# mpp_bldc.net
KiCad netlist of a schematic drawn in EAGLE
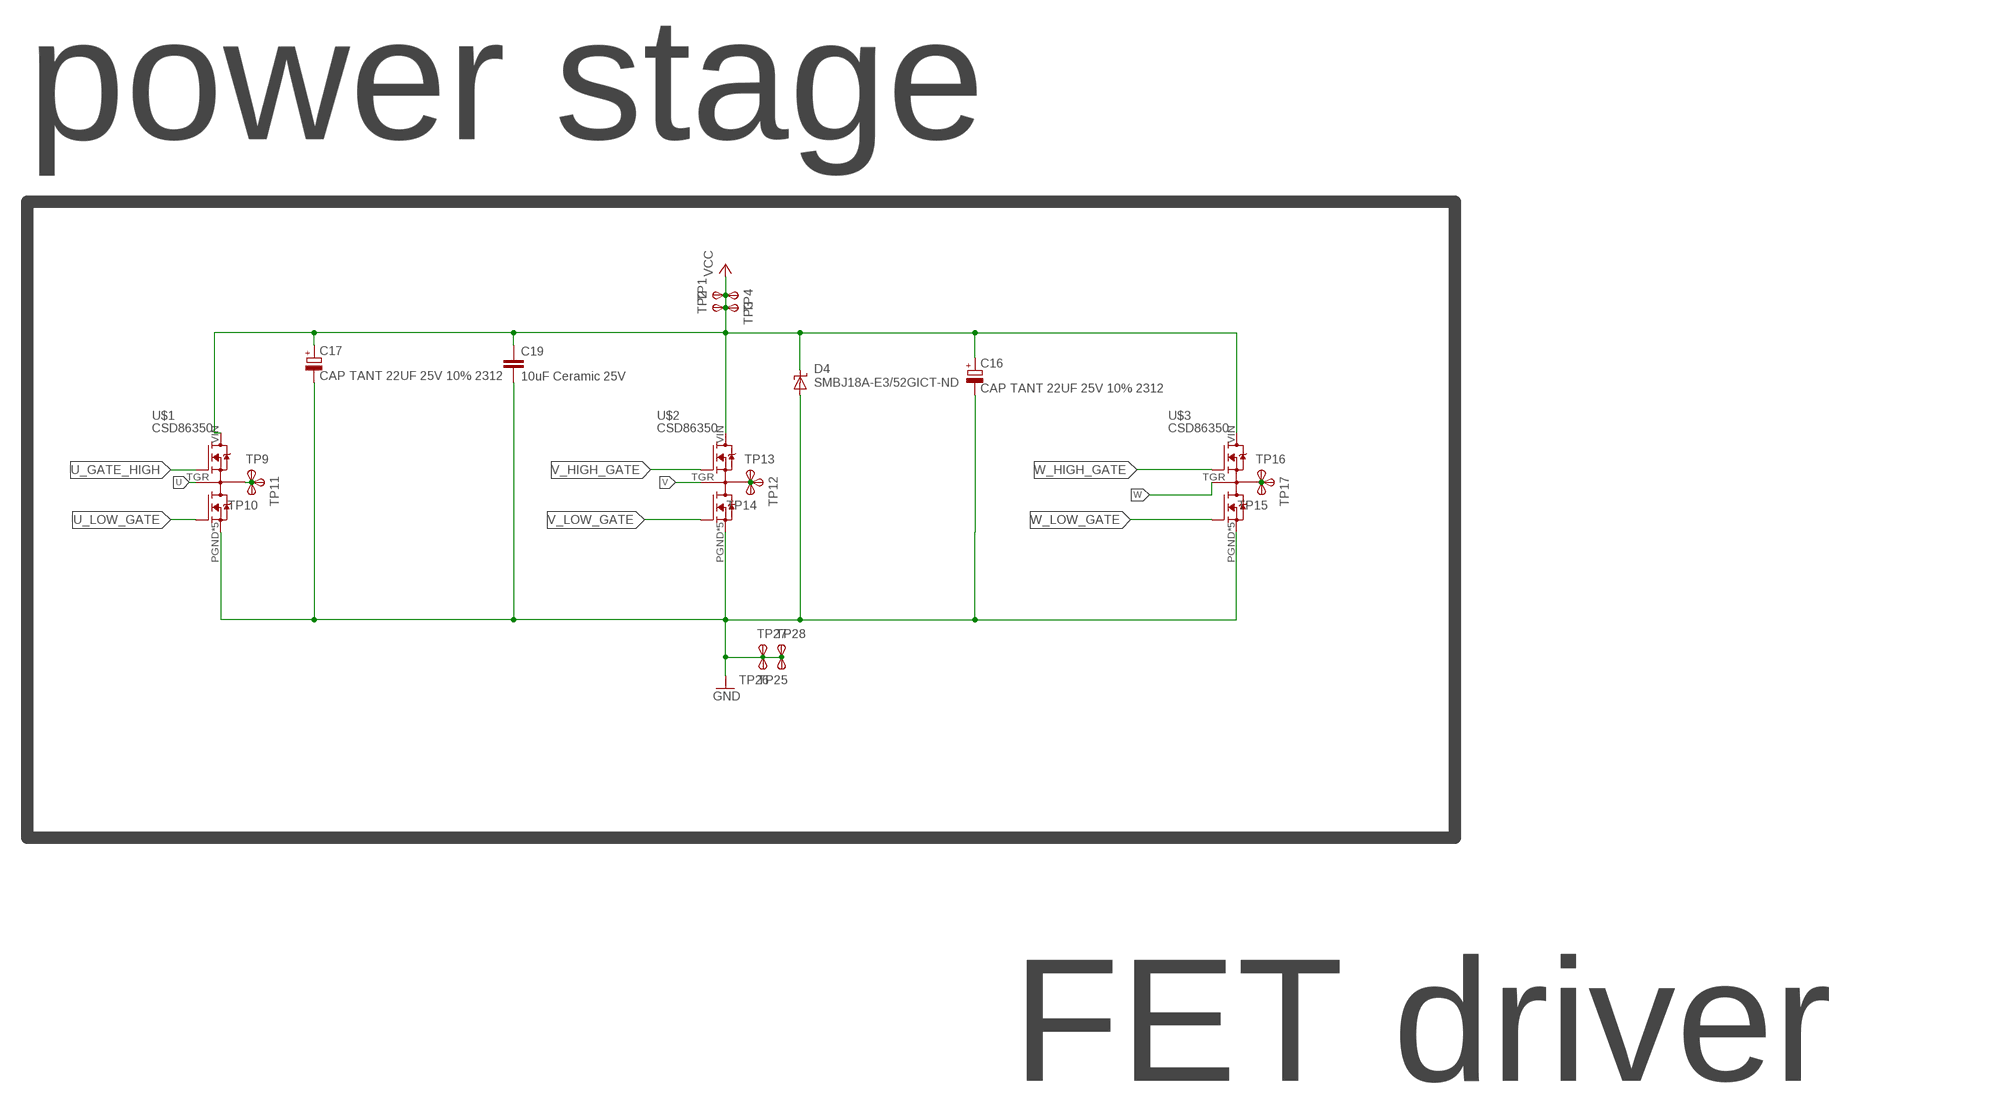
[diagram p0: schematic, sheet 1, part 1 of 2]
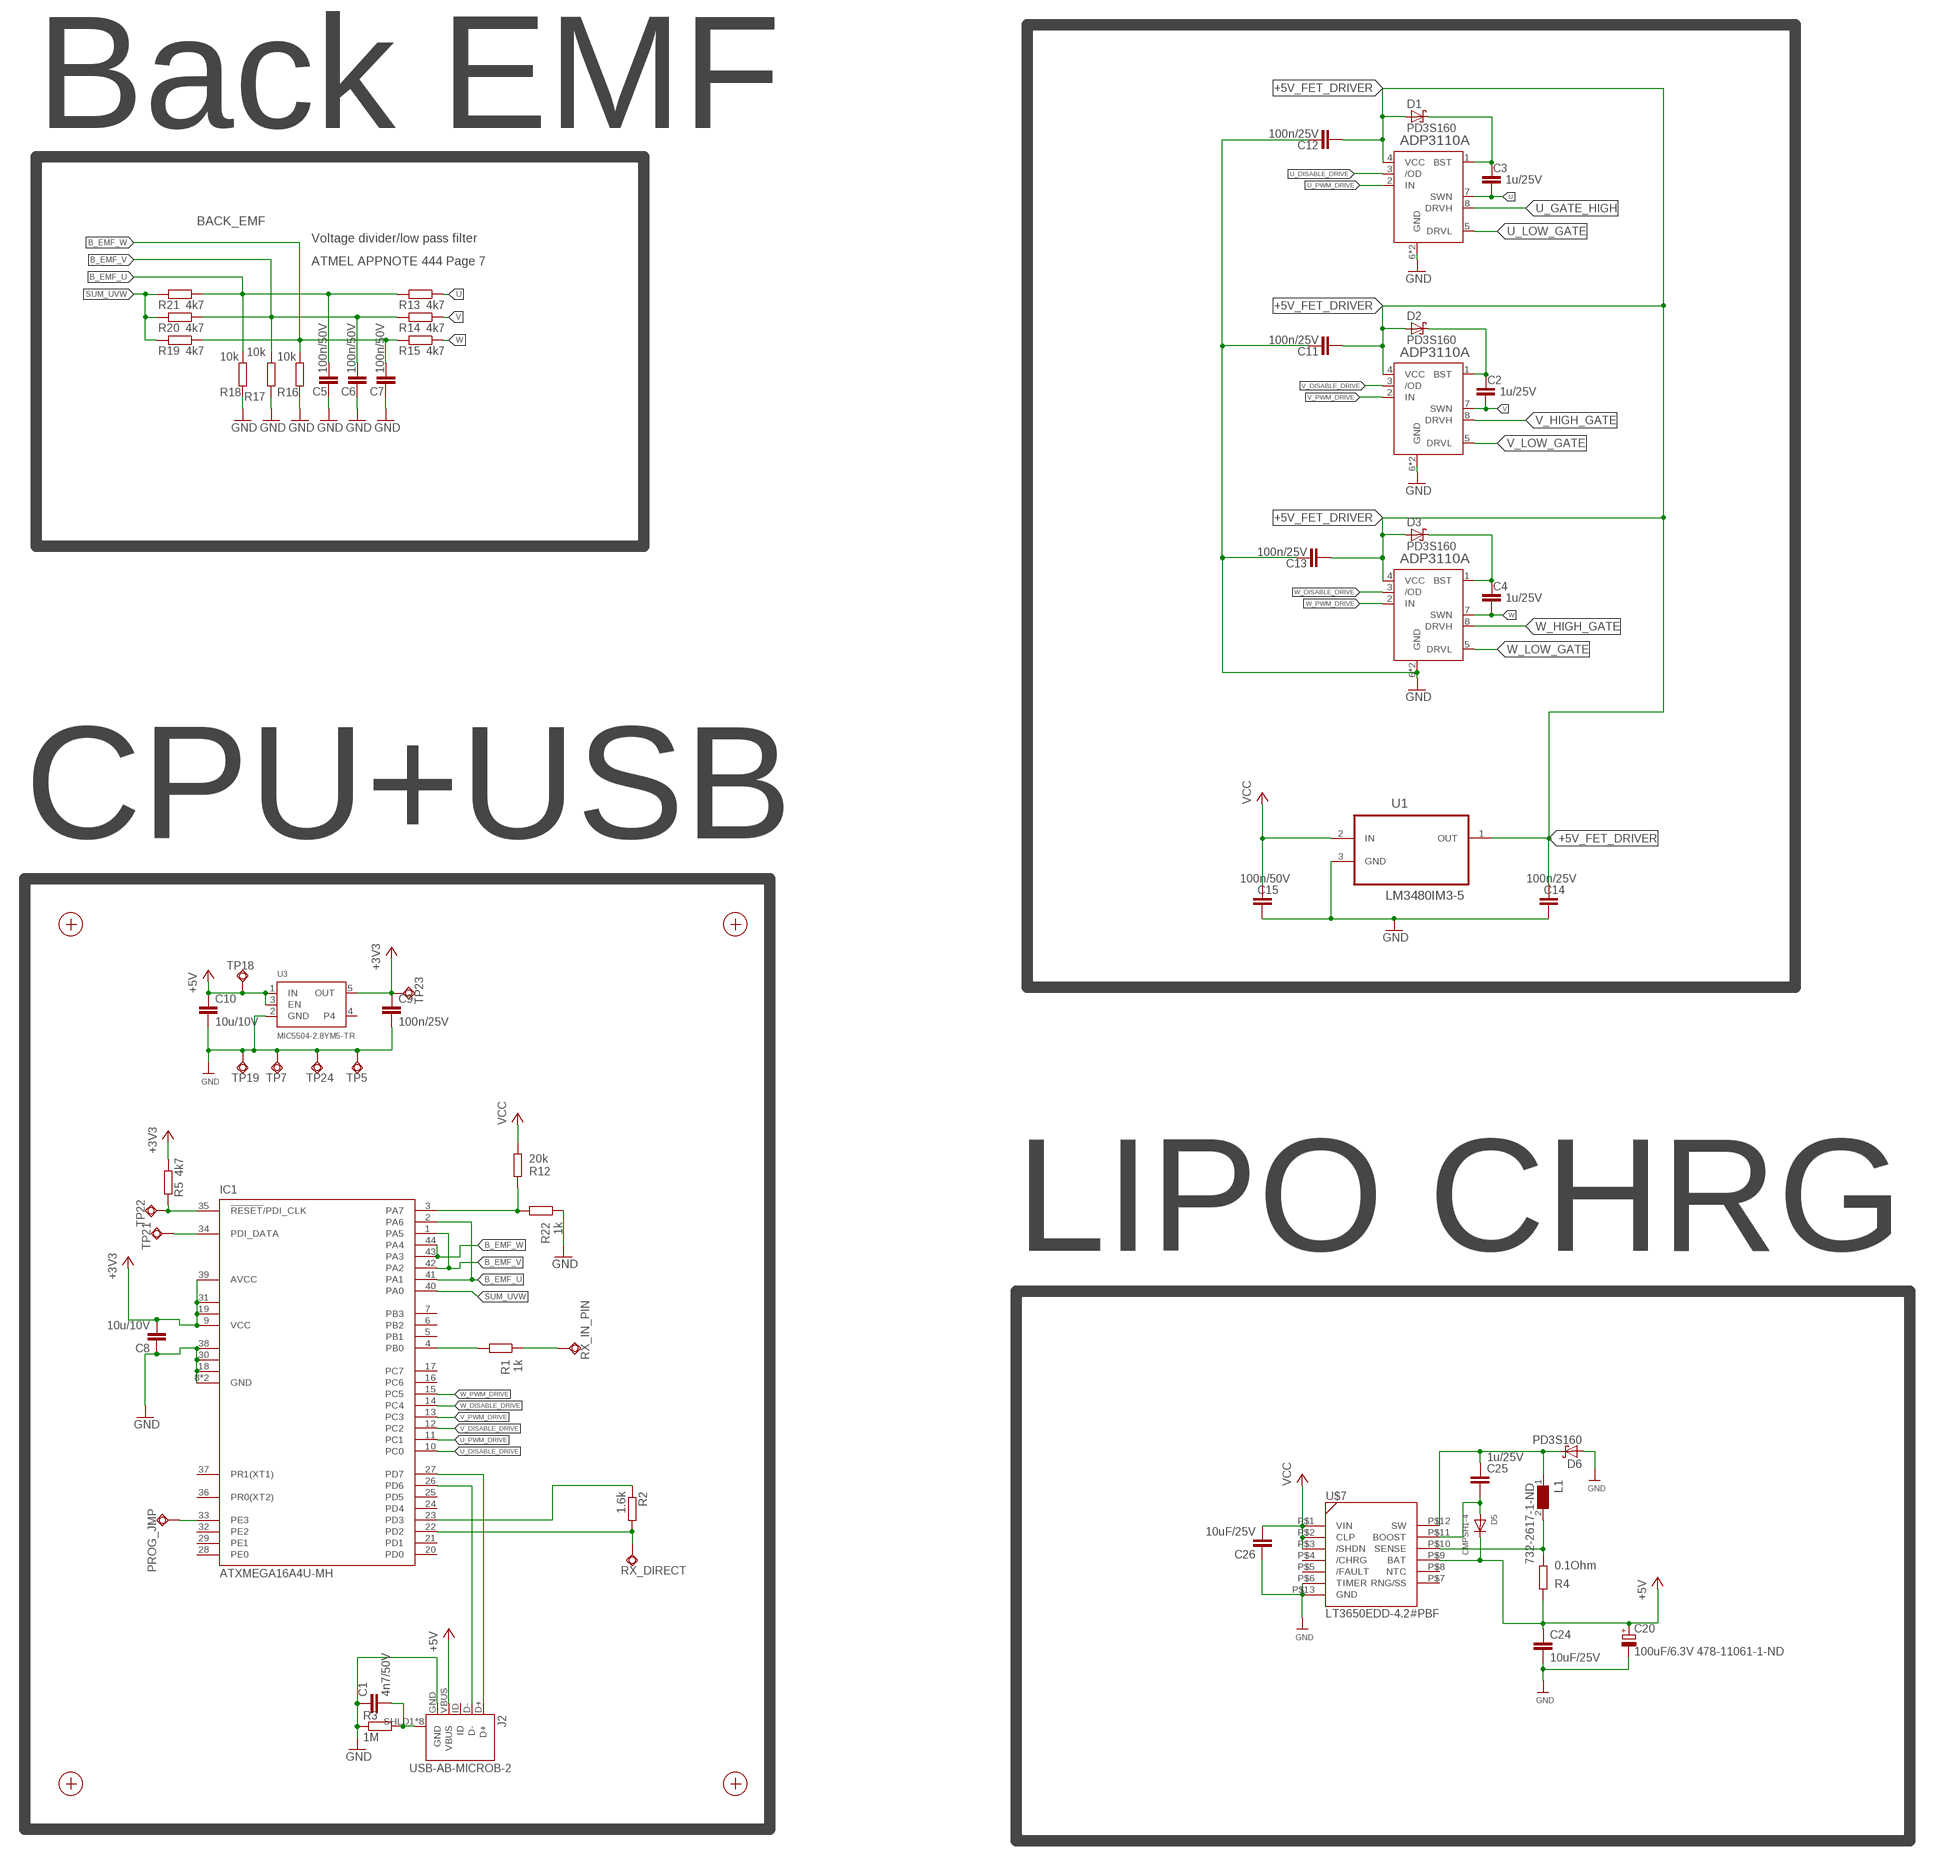
[diagram p1: schematic, sheet 1, part 2 of 2]

(export (version "E")
  (design (tool "Eeschema 10.0.6"))
  (components
    (comp (ref "C1")
      (value "4n7/50V")
      (footprint "eagle-import:C0603")
      (libsource (lib "eagle-import") (part "C-EUC0603"))
    )
    (comp (ref "C2")
      (value "1u/25V")
      (footprint "eagle-import:C0603")
      (libsource (lib "eagle-import") (part "C-EUC0603"))
    )
    (comp (ref "C3")
      (value "1u/25V")
      (footprint "eagle-import:C0603")
      (libsource (lib "eagle-import") (part "C-EUC0603"))
    )
    (comp (ref "C4")
      (value "1u/25V")
      (footprint "eagle-import:C0603")
      (libsource (lib "eagle-import") (part "C-EUC0603"))
    )
    (comp (ref "C5")
      (value "100n/50V")
      (footprint "eagle-import:C0603")
      (libsource (lib "eagle-import") (part "C-EUC0603"))
    )
    (comp (ref "C6")
      (value "100n/50V")
      (footprint "eagle-import:C0603")
      (libsource (lib "eagle-import") (part "C-EUC0603"))
    )
    (comp (ref "C7")
      (value "100n/50V")
      (footprint "eagle-import:C0603")
      (libsource (lib "eagle-import") (part "C-EUC0603"))
    )
    (comp (ref "C8")
      (value "10u/10V")
      (footprint "eagle-import:C0603K")
      (libsource (lib "eagle-import") (part "C-EUC0603K"))
    )
    (comp (ref "C9")
      (value "100n/25V")
      (footprint "eagle-import:C0603")
      (libsource (lib "eagle-import") (part "C-EUC0603"))
    )
    (comp (ref "C10")
      (value "10u/10V")
      (footprint "eagle-import:C0603K")
      (libsource (lib "eagle-import") (part "C-EUC0603K"))
    )
    (comp (ref "C11")
      (value "100n/25V")
      (footprint "eagle-import:C0603")
      (libsource (lib "eagle-import") (part "C-EUC0603"))
    )
    (comp (ref "C12")
      (value "100n/25V")
      (footprint "eagle-import:C0603")
      (libsource (lib "eagle-import") (part "C-EUC0603"))
    )
    (comp (ref "C13")
      (value "100n/25V")
      (footprint "eagle-import:C0603")
      (libsource (lib "eagle-import") (part "C-EUC0603"))
    )
    (comp (ref "C14")
      (value "100n/25V")
      (footprint "eagle-import:C0603")
      (libsource (lib "eagle-import") (part "C-EUC0603"))
    )
    (comp (ref "C15")
      (value "100n/50V")
      (footprint "eagle-import:C0603")
      (libsource (lib "eagle-import") (part "C-EUC0603"))
    )
    (comp (ref "C16")
      (value "CAP TANT 22UF 25V 10% 2312")
      (footprint "eagle-import:C_6032-28R")
      (libsource (lib "eagle-import") (part "CPOL-EUC/6032-28R"))
    )
    (comp (ref "C17")
      (value "CAP TANT 22UF 25V 10% 2312")
      (footprint "eagle-import:C_6032-28R")
      (libsource (lib "eagle-import") (part "CPOL-EUC/6032-28R"))
    )
    (comp (ref "C19")
      (value "10uF Ceramic 25V")
      (footprint "eagle-import:C1206")
      (libsource (lib "eagle-import") (part "rcl_334_C-EUC1206"))
    )
    (comp (ref "C20")
      (value "100uF/6.3V 478-11061-1-ND")
      (footprint "eagle-import:CT7343")
      (libsource (lib "eagle-import") (part "CPOL-EUCT7343"))
    )
    (comp (ref "C24")
      (value "10uF/25V")
      (footprint "eagle-import:C0805")
      (libsource (lib "eagle-import") (part "C-EUC0805"))
    )
    (comp (ref "C25")
      (value "1u/25V")
      (footprint "eagle-import:C0603")
      (libsource (lib "eagle-import") (part "C-EUC0603"))
    )
    (comp (ref "C26")
      (value "10uF/25V")
      (footprint "eagle-import:C0805")
      (libsource (lib "eagle-import") (part "C-EUC0805"))
    )
    (comp (ref "D1")
      (value "PD3S160")
      (footprint "eagle-import:POWERDI323")
      (libsource (lib "eagle-import") (part "mpp_bldc_ng_2_PD3S160"))
    )
    (comp (ref "D2")
      (value "PD3S160")
      (footprint "eagle-import:POWERDI323")
      (libsource (lib "eagle-import") (part "mpp_bldc_ng_2_PD3S160"))
    )
    (comp (ref "D3")
      (value "PD3S160")
      (footprint "eagle-import:POWERDI323")
      (libsource (lib "eagle-import") (part "mpp_bldc_ng_2_PD3S160"))
    )
    (comp (ref "D4")
      (value "SMBJ18A-E3/52GICT-ND")
      (footprint "eagle-import:SMBJ")
      (libsource (lib "eagle-import") (part "SUPPRESSOR-SMBJ"))
    )
    (comp (ref "D5")
      (value "CMPSH1-4")
      (footprint "eagle-import:SOT23-R")
      (libsource (lib "eagle-import") (part "DIODESOT23_REFLOW"))
    )
    (comp (ref "D6")
      (value "PD3S160")
      (footprint "eagle-import:POWERDI323")
      (libsource (lib "eagle-import") (part "PD3S160"))
    )
    (comp (ref "IC1")
      (value "ATXMEGA16A4U-MH")
      (footprint "eagle-import:MLF44-TH")
      (libsource (lib "eagle-import") (part "XMEGA16A4M1"))
    )
    (comp (ref "J2")
      (value "USB-AB-MICROB-2")
      (footprint "eagle-import:USB-MICROB-10118194")
      (libsource (lib "eagle-import") (part "USB-AB-MICROB-2"))
    )
    (comp (ref "L1")
      (value "732-2617-1-ND")
      (footprint "eagle-import:WE-TPC_2828")
      (fields (field (name "MPN") "744025001"))
      (libsource (lib "eagle-import") (part "WE-TPC_2828-744025001"))
    )
    (comp (ref "PROG_JMP")
      (value "TPSQTP19SQ")
      (footprint "eagle-import:TP19SQ")
      (libsource (lib "eagle-import") (part "TPSQTP19SQ"))
    )
    (comp (ref "R1")
      (value "1k")
      (footprint "eagle-import:R0603")
      (libsource (lib "eagle-import") (part "R-EU_R0603"))
    )
    (comp (ref "R2")
      (value "1.6k")
      (footprint "eagle-import:R0603")
      (libsource (lib "eagle-import") (part "resistor_R-EU_R0603"))
    )
    (comp (ref "R3")
      (value "1M")
      (footprint "eagle-import:R0603")
      (libsource (lib "eagle-import") (part "resistor_R-EU_R0603"))
    )
    (comp (ref "R4")
      (value "0.1Ohm")
      (footprint "eagle-import:R0402")
      (libsource (lib "eagle-import") (part "R-EU_R0402"))
    )
    (comp (ref "R5")
      (value "4k7")
      (footprint "eagle-import:R0603")
      (libsource (lib "eagle-import") (part "R-EU_R0603"))
    )
    (comp (ref "R12")
      (value "20k")
      (footprint "eagle-import:R0603")
      (libsource (lib "eagle-import") (part "R-EU_R0603"))
    )
    (comp (ref "R13")
      (value "4k7")
      (footprint "eagle-import:R0603")
      (libsource (lib "eagle-import") (part "R-EU_R0603"))
    )
    (comp (ref "R14")
      (value "4k7")
      (footprint "eagle-import:R0603")
      (libsource (lib "eagle-import") (part "R-EU_R0603"))
    )
    (comp (ref "R15")
      (value "4k7")
      (footprint "eagle-import:R0603")
      (libsource (lib "eagle-import") (part "R-EU_R0603"))
    )
    (comp (ref "R16")
      (value "10k")
      (footprint "eagle-import:R0603")
      (libsource (lib "eagle-import") (part "R-EU_R0603"))
    )
    (comp (ref "R17")
      (value "10k")
      (footprint "eagle-import:R0603")
      (libsource (lib "eagle-import") (part "R-EU_R0603"))
    )
    (comp (ref "R18")
      (value "10k")
      (footprint "eagle-import:R0603")
      (libsource (lib "eagle-import") (part "R-EU_R0603"))
    )
    (comp (ref "R19")
      (value "4k7")
      (footprint "eagle-import:R0603")
      (libsource (lib "eagle-import") (part "R-EU_R0603"))
    )
    (comp (ref "R20")
      (value "4k7")
      (footprint "eagle-import:R0603")
      (libsource (lib "eagle-import") (part "R-EU_R0603"))
    )
    (comp (ref "R21")
      (value "4k7")
      (footprint "eagle-import:R0603")
      (libsource (lib "eagle-import") (part "R-EU_R0603"))
    )
    (comp (ref "R22")
      (value "1k")
      (footprint "eagle-import:R0603")
      (libsource (lib "eagle-import") (part "R-EU_R0603"))
    )
    (comp (ref "RX_DIRECT")
      (value "TPSQTP19SQ")
      (footprint "eagle-import:TP19SQ")
      (libsource (lib "eagle-import") (part "TPSQTP19SQ"))
    )
    (comp (ref "RX_IN_PIN")
      (value "TPSQTP19SQ")
      (footprint "eagle-import:TP19SQ")
      (libsource (lib "eagle-import") (part "TPSQTP19SQ"))
    )
    (comp (ref "TP1")
      (value "TPSTP20SQ")
      (footprint "eagle-import:TP20SQ")
      (libsource (lib "eagle-import") (part "TPSTP20SQ"))
    )
    (comp (ref "TP2")
      (value "TPSTP20SQ")
      (footprint "eagle-import:TP20SQ")
      (libsource (lib "eagle-import") (part "TPSTP20SQ"))
    )
    (comp (ref "TP3")
      (value "TPSTP20SQ")
      (footprint "eagle-import:TP20SQ")
      (libsource (lib "eagle-import") (part "TPSTP20SQ"))
    )
    (comp (ref "TP4")
      (value "TPSTP20SQ")
      (footprint "eagle-import:TP20SQ")
      (libsource (lib "eagle-import") (part "TPSTP20SQ"))
    )
    (comp (ref "TP5")
      (value "TPSQTP19SQ")
      (footprint "eagle-import:TP19SQ")
      (libsource (lib "eagle-import") (part "TPSQTP19SQ"))
    )
    (comp (ref "TP7")
      (value "TPSQTP19SQ")
      (footprint "eagle-import:TP19SQ")
      (libsource (lib "eagle-import") (part "TPSQTP19SQ"))
    )
    (comp (ref "TP9")
      (value "TPSTP20SQ")
      (footprint "eagle-import:TP20SQ")
      (libsource (lib "eagle-import") (part "TPSTP20SQ"))
    )
    (comp (ref "TP10")
      (value "TPSTP20SQ")
      (footprint "eagle-import:TP20SQ")
      (libsource (lib "eagle-import") (part "TPSTP20SQ"))
    )
    (comp (ref "TP11")
      (value "TPSTP20SQ")
      (footprint "eagle-import:TP20SQ")
      (libsource (lib "eagle-import") (part "TPSTP20SQ"))
    )
    (comp (ref "TP12")
      (value "TPSTP20SQ")
      (footprint "eagle-import:TP20SQ")
      (libsource (lib "eagle-import") (part "TPSTP20SQ"))
    )
    (comp (ref "TP13")
      (value "TPSTP20SQ")
      (footprint "eagle-import:TP20SQ")
      (libsource (lib "eagle-import") (part "TPSTP20SQ"))
    )
    (comp (ref "TP14")
      (value "TPSTP20SQ")
      (footprint "eagle-import:TP20SQ")
      (libsource (lib "eagle-import") (part "TPSTP20SQ"))
    )
    (comp (ref "TP15")
      (value "TPSTP20SQ")
      (footprint "eagle-import:TP20SQ")
      (libsource (lib "eagle-import") (part "TPSTP20SQ"))
    )
    (comp (ref "TP16")
      (value "TPSTP20SQ")
      (footprint "eagle-import:TP20SQ")
      (libsource (lib "eagle-import") (part "TPSTP20SQ"))
    )
    (comp (ref "TP17")
      (value "TPSTP20SQ")
      (footprint "eagle-import:TP20SQ")
      (libsource (lib "eagle-import") (part "TPSTP20SQ"))
    )
    (comp (ref "TP18")
      (value "TPSQTP19SQ")
      (footprint "eagle-import:TP19SQ")
      (libsource (lib "eagle-import") (part "TPSQTP19SQ"))
    )
    (comp (ref "TP19")
      (value "TPSQTP19SQ")
      (footprint "eagle-import:TP19SQ")
      (libsource (lib "eagle-import") (part "TPSQTP19SQ"))
    )
    (comp (ref "TP21")
      (value "TPSQTP15R")
      (footprint "eagle-import:TP15R")
      (libsource (lib "eagle-import") (part "TPSQTP15R"))
    )
    (comp (ref "TP22")
      (value "TPSQTP14SQ")
      (footprint "eagle-import:TP14SQ")
      (libsource (lib "eagle-import") (part "TPSQTP14SQ"))
    )
    (comp (ref "TP23")
      (value "TPSQTP14SQ")
      (footprint "eagle-import:TP14SQ")
      (libsource (lib "eagle-import") (part "TPSQTP14SQ"))
    )
    (comp (ref "TP24")
      (value "TPSQTP14SQ")
      (footprint "eagle-import:TP14SQ")
      (libsource (lib "eagle-import") (part "TPSQTP14SQ"))
    )
    (comp (ref "TP25")
      (value "TPSTP20SQ")
      (footprint "eagle-import:TP20SQ")
      (libsource (lib "eagle-import") (part "TPSTP20SQ"))
    )
    (comp (ref "TP26")
      (value "TPSTP20SQ")
      (footprint "eagle-import:TP20SQ")
      (libsource (lib "eagle-import") (part "TPSTP20SQ"))
    )
    (comp (ref "TP27")
      (value "TPSTP20SQ")
      (footprint "eagle-import:TP20SQ")
      (libsource (lib "eagle-import") (part "TPSTP20SQ"))
    )
    (comp (ref "TP28")
      (value "TPSTP20SQ")
      (footprint "eagle-import:TP20SQ")
      (libsource (lib "eagle-import") (part "TPSTP20SQ"))
    )
    (comp (ref "U$1")
      (value "CSD86350")
      (footprint "eagle-import:Q5D")
      (libsource (lib "eagle-import") (part "CSD86350"))
    )
    (comp (ref "U$2")
      (value "CSD86350")
      (footprint "eagle-import:Q5D")
      (libsource (lib "eagle-import") (part "CSD86350"))
    )
    (comp (ref "U$3")
      (value "CSD86350")
      (footprint "eagle-import:Q5D")
      (libsource (lib "eagle-import") (part "CSD86350"))
    )
    (comp (ref "U$4")
      (value "ADP3110A")
      (footprint "eagle-import:DFN-8")
      (libsource (lib "eagle-import") (part "ADP3110A"))
    )
    (comp (ref "U$5")
      (value "ADP3110A")
      (footprint "eagle-import:DFN-8")
      (libsource (lib "eagle-import") (part "ADP3110A"))
    )
    (comp (ref "U$6")
      (value "ADP3110A")
      (footprint "eagle-import:DFN-8")
      (libsource (lib "eagle-import") (part "ADP3110A"))
    )
    (comp (ref "U$7")
      (value "LT3650EDD-4.2#PBF")
      (footprint "eagle-import:12-WFDFN")
      (libsource (lib "eagle-import") (part "LT3650-4.2"))
    )
    (comp (ref "U1")
      (value "LM3480IM3-5")
      (footprint "eagle-import:SOT95P251X112-3N")
      (fields (field (name "MPN") "LM3480IM3-12"))
      (libsource (lib "eagle-import") (part "LM3480IM3-12"))
    )
    (comp (ref "U3")
      (value "MIC5504-2.8YM5-TR")
      (footprint "eagle-import:SOT23-5")
      (libsource (lib "eagle-import") (part "VREG_SOT23-5"))
    )
    (comp (ref "X1")
      (value "PASSER-07")
      (footprint "eagle-import:PASSER_07MM")
      (libsource (lib "eagle-import") (part "PASSER-07"))
    )
    (comp (ref "X2")
      (value "PASSER-07")
      (footprint "eagle-import:PASSER_07MM")
      (libsource (lib "eagle-import") (part "PASSER-07"))
    )
    (comp (ref "X3")
      (value "PASSER-07")
      (footprint "eagle-import:PASSER_07MM")
      (libsource (lib "eagle-import") (part "PASSER-07"))
    )
    (comp (ref "X4")
      (value "PASSER-07")
      (footprint "eagle-import:PASSER_07MM")
      (libsource (lib "eagle-import") (part "PASSER-07"))
    )
  )
  (nets
    (net (code "1") (name "+3V3") (class "Default")
      (node (ref "C8") (pin "2") (pinfunction "2_2") (pintype "passive"))
      (node (ref "C9") (pin "1") (pinfunction "1_1") (pintype "passive"))
      (node (ref "IC1") (pin "19") (pinfunction "VCC1_19") (pintype "power_in"))
      (node (ref "IC1") (pin "31") (pinfunction "VCC2_31") (pintype "power_in"))
      (node (ref "IC1") (pin "39") (pinfunction "AVCC_39") (pintype "power_in"))
      (node (ref "IC1") (pin "9") (pinfunction "VCC_9") (pintype "power_in"))
      (node (ref "R5") (pin "1") (pinfunction "1_1") (pintype "passive"))
      (node (ref "TP23") (pin "TP") (pinfunction "TP_TP") (pintype "input"))
      (node (ref "U3") (pin "5") (pinfunction "OUT_5") (pintype "bidirectional"))
    )
    (net (code "2") (name "+5V") (class "Default")
      (node (ref "C10") (pin "1") (pinfunction "1_1") (pintype "passive"))
      (node (ref "C20") (pin "+") (pinfunction "+_+") (pintype "passive"))
      (node (ref "C24") (pin "1") (pinfunction "1_1") (pintype "passive"))
      (node (ref "D5") (pin "3") (pinfunction "C_3") (pintype "passive"))
      (node (ref "J2") (pin "VBUS") (pinfunction "VBUS_VBUS") (pintype "power_in"))
      (node (ref "R4") (pin "2") (pinfunction "2_2") (pintype "passive"))
      (node (ref "TP18") (pin "TP") (pinfunction "TP_TP") (pintype "input"))
      (node (ref "U$7") (pin "P$9") (pinfunction "BAT_P$9") (pintype "bidirectional"))
      (node (ref "U3") (pin "1") (pinfunction "IN_1") (pintype "bidirectional"))
      (node (ref "U3") (pin "3") (pinfunction "EN_3") (pintype "bidirectional"))
    )
    (net (code "3") (name "+5V_FET_DRIVER") (class "Default")
      (node (ref "C11") (pin "2") (pinfunction "2_2") (pintype "passive"))
      (node (ref "C12") (pin "2") (pinfunction "2_2") (pintype "passive"))
      (node (ref "C13") (pin "2") (pinfunction "2_2") (pintype "passive"))
      (node (ref "C14") (pin "2") (pinfunction "2_2") (pintype "passive"))
      (node (ref "D1") (pin "A") (pinfunction "A_A") (pintype "passive"))
      (node (ref "D2") (pin "A") (pinfunction "A_A") (pintype "passive"))
      (node (ref "D3") (pin "A") (pinfunction "A_A") (pintype "passive"))
      (node (ref "U$4") (pin "4") (pinfunction "VCC_4") (pintype "passive"))
      (node (ref "U$5") (pin "4") (pinfunction "VCC_4") (pintype "passive"))
      (node (ref "U$6") (pin "4") (pinfunction "VCC_4") (pintype "passive"))
      (node (ref "U1") (pin "1") (pinfunction "OUT_1") (pintype "output"))
    )
    (net (code "4") (name "B_EMF_U") (class "Default")
      (node (ref "C5") (pin "1") (pinfunction "1_1") (pintype "passive"))
      (node (ref "IC1") (pin "2") (pinfunction "PA6_2") (pintype "bidirectional"))
      (node (ref "IC1") (pin "41") (pinfunction "PA1_41") (pintype "bidirectional"))
      (node (ref "R13") (pin "2") (pinfunction "2_2") (pintype "passive"))
      (node (ref "R18") (pin "1") (pinfunction "1_1") (pintype "passive"))
      (node (ref "R21") (pin "1") (pinfunction "1_1") (pintype "passive"))
    )
    (net (code "5") (name "B_EMF_V") (class "Default")
      (node (ref "C6") (pin "1") (pinfunction "1_1") (pintype "passive"))
      (node (ref "IC1") (pin "1") (pinfunction "PA5_1") (pintype "bidirectional"))
      (node (ref "IC1") (pin "42") (pinfunction "PA2_42") (pintype "bidirectional"))
      (node (ref "R14") (pin "2") (pinfunction "2_2") (pintype "passive"))
      (node (ref "R17") (pin "1") (pinfunction "1_1") (pintype "passive"))
      (node (ref "R20") (pin "1") (pinfunction "1_1") (pintype "passive"))
    )
    (net (code "6") (name "B_EMF_W") (class "Default")
      (node (ref "C7") (pin "1") (pinfunction "1_1") (pintype "passive"))
      (node (ref "IC1") (pin "43") (pinfunction "PA3_43") (pintype "bidirectional"))
      (node (ref "IC1") (pin "44") (pinfunction "PA4_44") (pintype "bidirectional"))
      (node (ref "R15") (pin "2") (pinfunction "2_2") (pintype "passive"))
      (node (ref "R16") (pin "1") (pinfunction "1_1") (pintype "passive"))
      (node (ref "R19") (pin "1") (pinfunction "1_1") (pintype "passive"))
    )
    (net (code "7") (name "GND") (class "Default")
      (node (ref "C1") (pin "1") (pinfunction "1_1") (pintype "passive"))
      (node (ref "C10") (pin "2") (pinfunction "2_2") (pintype "passive"))
      (node (ref "C11") (pin "1") (pinfunction "1_1") (pintype "passive"))
      (node (ref "C12") (pin "1") (pinfunction "1_1") (pintype "passive"))
      (node (ref "C13") (pin "1") (pinfunction "1_1") (pintype "passive"))
      (node (ref "C14") (pin "1") (pinfunction "1_1") (pintype "passive"))
      (node (ref "C15") (pin "1") (pinfunction "1_1") (pintype "passive"))
      (node (ref "C16") (pin "-") (pinfunction "-_-") (pintype "passive"))
      (node (ref "C17") (pin "-") (pinfunction "-_-") (pintype "passive"))
      (node (ref "C19") (pin "2") (pinfunction "2_2") (pintype "passive"))
      (node (ref "C20") (pin "-") (pinfunction "-_-") (pintype "passive"))
      (node (ref "C24") (pin "2") (pinfunction "2_2") (pintype "passive"))
      (node (ref "C26") (pin "1") (pinfunction "1_1") (pintype "passive"))
      (node (ref "C5") (pin "2") (pinfunction "2_2") (pintype "passive"))
      (node (ref "C6") (pin "2") (pinfunction "2_2") (pintype "passive"))
      (node (ref "C7") (pin "2") (pinfunction "2_2") (pintype "passive"))
      (node (ref "C8") (pin "1") (pinfunction "1_1") (pintype "passive"))
      (node (ref "C9") (pin "2") (pinfunction "2_2") (pintype "passive"))
      (node (ref "D4") (pin "A") (pinfunction "A_A") (pintype "passive"))
      (node (ref "D6") (pin "A") (pinfunction "A_A") (pintype "passive"))
      (node (ref "IC1") (pin "18") (pinfunction "GND1_18") (pintype "power_in"))
      (node (ref "IC1") (pin "30") (pinfunction "GND2_30") (pintype "power_in"))
      (node (ref "IC1") (pin "38") (pinfunction "GND3_38") (pintype "power_in"))
      (node (ref "IC1") (pin "8") (pinfunction "GND_8") (pintype "power_in"))
      (node (ref "IC1") (pin "TH") (pinfunction "GND_TH") (pintype "power_in"))
      (node (ref "J2") (pin "GND") (pinfunction "GND_GND") (pintype "power_in"))
      (node (ref "R16") (pin "2") (pinfunction "2_2") (pintype "passive"))
      (node (ref "R17") (pin "2") (pinfunction "2_2") (pintype "passive"))
      (node (ref "R18") (pin "2") (pinfunction "2_2") (pintype "passive"))
      (node (ref "R22") (pin "1") (pinfunction "1_1") (pintype "passive"))
      (node (ref "R3") (pin "1") (pinfunction "1_1") (pintype "passive"))
      (node (ref "TP19") (pin "TP") (pinfunction "TP_TP") (pintype "input"))
      (node (ref "TP24") (pin "TP") (pinfunction "TP_TP") (pintype "input"))
      (node (ref "TP25") (pin "TP") (pinfunction "PP_TP") (pintype "input"))
      (node (ref "TP26") (pin "TP") (pinfunction "PP_TP") (pintype "input"))
      (node (ref "TP27") (pin "TP") (pinfunction "PP_TP") (pintype "input"))
      (node (ref "TP28") (pin "TP") (pinfunction "PP_TP") (pintype "input"))
      (node (ref "TP5") (pin "TP") (pinfunction "TP_TP") (pintype "input"))
      (node (ref "TP7") (pin "TP") (pinfunction "TP_TP") (pintype "input"))
      (node (ref "U$1") (pin "PGND") (pinfunction "PGND_PGND") (pintype "passive"))
      (node (ref "U$1") (pin "PGND0") (pinfunction "PGND_PGND0") (pintype "passive"))
      (node (ref "U$1") (pin "PGND1") (pinfunction "PGND_PGND1") (pintype "passive"))
      (node (ref "U$1") (pin "PGND2") (pinfunction "PGND_PGND2") (pintype "passive"))
      (node (ref "U$1") (pin "PGND3") (pinfunction "PGND_PGND3") (pintype "passive"))
      (node (ref "U$2") (pin "PGND") (pinfunction "PGND_PGND") (pintype "passive"))
      (node (ref "U$2") (pin "PGND0") (pinfunction "PGND_PGND0") (pintype "passive"))
      (node (ref "U$2") (pin "PGND1") (pinfunction "PGND_PGND1") (pintype "passive"))
      (node (ref "U$2") (pin "PGND2") (pinfunction "PGND_PGND2") (pintype "passive"))
      (node (ref "U$2") (pin "PGND3") (pinfunction "PGND_PGND3") (pintype "passive"))
      (node (ref "U$3") (pin "PGND") (pinfunction "PGND_PGND") (pintype "passive"))
      (node (ref "U$3") (pin "PGND0") (pinfunction "PGND_PGND0") (pintype "passive"))
      (node (ref "U$3") (pin "PGND1") (pinfunction "PGND_PGND1") (pintype "passive"))
      (node (ref "U$3") (pin "PGND2") (pinfunction "PGND_PGND2") (pintype "passive"))
      (node (ref "U$3") (pin "PGND3") (pinfunction "PGND_PGND3") (pintype "passive"))
      (node (ref "U$4") (pin "6") (pinfunction "GND_6") (pintype "passive"))
      (node (ref "U$4") (pin "PAD") (pinfunction "GND_PAD") (pintype "passive"))
      (node (ref "U$5") (pin "6") (pinfunction "GND_6") (pintype "passive"))
      (node (ref "U$5") (pin "PAD") (pinfunction "GND_PAD") (pintype "passive"))
      (node (ref "U$6") (pin "6") (pinfunction "GND_6") (pintype "passive"))
      (node (ref "U$6") (pin "PAD") (pinfunction "GND_PAD") (pintype "passive"))
      (node (ref "U$7") (pin "P$13") (pinfunction "GND_P$13") (pintype "power_in"))
      (node (ref "U$7") (pin "P$6") (pinfunction "TIMER_P$6") (pintype "bidirectional"))
      (node (ref "U1") (pin "3") (pinfunction "GND_3") (pintype "passive"))
      (node (ref "U3") (pin "2") (pinfunction "GND_2") (pintype "bidirectional"))
    )
    (net (code "8") (name "Net-(C1-Pad2)") (class "Default")
      (node (ref "C1") (pin "2") (pinfunction "2_2") (pintype "passive"))
      (node (ref "J2") (pin "SHLD1") (pinfunction "SHIELD_SHLD1") (pintype "passive"))
      (node (ref "J2") (pin "SHLD2") (pinfunction "SHIELD_SHLD2") (pintype "passive"))
      (node (ref "J2") (pin "SHLD3") (pinfunction "SHIELD_SHLD3") (pintype "passive"))
      (node (ref "J2") (pin "SHLD4") (pinfunction "SHIELD_SHLD4") (pintype "passive"))
      (node (ref "J2") (pin "SHLD5") (pinfunction "SHIELD_SHLD5") (pintype "passive"))
      (node (ref "J2") (pin "SHLD6") (pinfunction "SHIELD_SHLD6") (pintype "passive"))
      (node (ref "J2") (pin "SHLD7") (pinfunction "SHIELD_SHLD7") (pintype "passive"))
      (node (ref "J2") (pin "SHLD8") (pinfunction "SHIELD_SHLD8") (pintype "passive"))
      (node (ref "R3") (pin "2") (pinfunction "2_2") (pintype "passive"))
    )
    (net (code "9") (name "Net-(D5-A)") (class "Default")
      (node (ref "C25") (pin "2") (pinfunction "2_2") (pintype "passive"))
      (node (ref "D5") (pin "1") (pinfunction "A_1") (pintype "passive"))
      (node (ref "U$7") (pin "P$11") (pinfunction "BOOST_P$11") (pintype "bidirectional"))
    )
    (net (code "10") (name "Net-(IC1-PA7)") (class "Default")
      (node (ref "IC1") (pin "3") (pinfunction "PA7_3") (pintype "bidirectional"))
      (node (ref "R12") (pin "2") (pinfunction "2_2") (pintype "passive"))
      (node (ref "R22") (pin "2") (pinfunction "2_2") (pintype "passive"))
    )
    (net (code "11") (name "Net-(IC1-PB0)") (class "Default")
      (node (ref "IC1") (pin "4") (pinfunction "PB0_4") (pintype "bidirectional"))
      (node (ref "R1") (pin "2") (pinfunction "2_2") (pintype "passive"))
    )
    (net (code "12") (name "Net-(IC1-PD2)") (class "Default")
      (node (ref "IC1") (pin "22") (pinfunction "PD2_22") (pintype "bidirectional"))
      (node (ref "R2") (pin "2") (pinfunction "2_2") (pintype "passive"))
      (node (ref "RX_DIRECT") (pin "TP") (pinfunction "TP_TP") (pintype "input"))
    )
    (net (code "13") (name "Net-(IC1-PD3)") (class "Default")
      (node (ref "IC1") (pin "23") (pinfunction "PD3_23") (pintype "bidirectional"))
      (node (ref "R2") (pin "1") (pinfunction "1_1") (pintype "passive"))
    )
    (net (code "14") (name "Net-(IC1-PD6)") (class "Default")
      (node (ref "IC1") (pin "26") (pinfunction "PD6_26") (pintype "bidirectional"))
      (node (ref "J2") (pin "D-") (pinfunction "D-_D-") (pintype "bidirectional"))
    )
    (net (code "15") (name "Net-(IC1-PD7)") (class "Default")
      (node (ref "IC1") (pin "27") (pinfunction "PD7_27") (pintype "bidirectional"))
      (node (ref "J2") (pin "D+") (pinfunction "D+_D+") (pintype "bidirectional"))
    )
    (net (code "16") (name "Net-(IC1-PDI_DATA)") (class "Default")
      (node (ref "IC1") (pin "34") (pinfunction "PDI_DATA_34") (pintype "bidirectional"))
      (node (ref "TP21") (pin "TP") (pinfunction "TP_TP") (pintype "input"))
    )
    (net (code "17") (name "Net-(IC1-PE3)") (class "Default")
      (node (ref "IC1") (pin "33") (pinfunction "PE3_33") (pintype "bidirectional"))
      (node (ref "PROG_JMP") (pin "TP") (pinfunction "TP_TP") (pintype "input"))
    )
    (net (code "18") (name "Net-(IC1-~{RESET}{slash}PDI_CLK)") (class "Default")
      (node (ref "IC1") (pin "35") (pinfunction "~{RESET}/PDI_CLK_35") (pintype "bidirectional"))
      (node (ref "R5") (pin "2") (pinfunction "2_2") (pintype "passive"))
      (node (ref "TP22") (pin "TP") (pinfunction "TP_TP") (pintype "input"))
    )
    (net (code "19") (name "Net-(R1-Pad1)") (class "Default")
      (node (ref "R1") (pin "1") (pinfunction "1_1") (pintype "passive"))
      (node (ref "RX_IN_PIN") (pin "TP") (pinfunction "TP_TP") (pintype "input"))
    )
    (net (code "20") (name "Net-(TP10-PP)") (class "Default")
      (node (ref "TP10") (pin "TP") (pinfunction "PP_TP") (pintype "input"))
      (node (ref "TP11") (pin "TP") (pinfunction "PP_TP") (pintype "input"))
      (node (ref "TP9") (pin "TP") (pinfunction "PP_TP") (pintype "input"))
      (node (ref "U$1") (pin "VSW0") (pinfunction "VSW_VSW0") (pintype "passive"))
      (node (ref "U$1") (pin "VSW1") (pinfunction "VSW_VSW1") (pintype "passive"))
      (node (ref "U$1") (pin "VSW2") (pinfunction "VSW_VSW2") (pintype "passive"))
    )
    (net (code "21") (name "Net-(TP12-PP)") (class "Default")
      (node (ref "TP12") (pin "TP") (pinfunction "PP_TP") (pintype "input"))
      (node (ref "TP13") (pin "TP") (pinfunction "PP_TP") (pintype "input"))
      (node (ref "TP14") (pin "TP") (pinfunction "PP_TP") (pintype "input"))
      (node (ref "U$2") (pin "VSW0") (pinfunction "VSW_VSW0") (pintype "passive"))
      (node (ref "U$2") (pin "VSW1") (pinfunction "VSW_VSW1") (pintype "passive"))
      (node (ref "U$2") (pin "VSW2") (pinfunction "VSW_VSW2") (pintype "passive"))
    )
    (net (code "22") (name "Net-(TP15-PP)") (class "Default")
      (node (ref "TP15") (pin "TP") (pinfunction "PP_TP") (pintype "input"))
      (node (ref "TP16") (pin "TP") (pinfunction "PP_TP") (pintype "input"))
      (node (ref "TP17") (pin "TP") (pinfunction "PP_TP") (pintype "input"))
      (node (ref "U$3") (pin "VSW0") (pinfunction "VSW_VSW0") (pintype "passive"))
      (node (ref "U$3") (pin "VSW1") (pinfunction "VSW_VSW1") (pintype "passive"))
      (node (ref "U$3") (pin "VSW2") (pinfunction "VSW_VSW2") (pintype "passive"))
    )
    (net (code "23") (name "Net-(U$4-BST)") (class "Default")
      (node (ref "C3") (pin "2") (pinfunction "2_2") (pintype "passive"))
      (node (ref "D1") (pin "C") (pinfunction "C_C") (pintype "passive"))
      (node (ref "U$4") (pin "1") (pinfunction "BST_1") (pintype "passive"))
    )
    (net (code "24") (name "Net-(U$5-BST)") (class "Default")
      (node (ref "C2") (pin "2") (pinfunction "2_2") (pintype "passive"))
      (node (ref "D2") (pin "C") (pinfunction "C_C") (pintype "passive"))
      (node (ref "U$5") (pin "1") (pinfunction "BST_1") (pintype "passive"))
    )
    (net (code "25") (name "Net-(U$6-BST)") (class "Default")
      (node (ref "C4") (pin "2") (pinfunction "2_2") (pintype "passive"))
      (node (ref "D3") (pin "C") (pinfunction "C_C") (pintype "passive"))
      (node (ref "U$6") (pin "1") (pinfunction "BST_1") (pintype "passive"))
    )
    (net (code "26") (name "Net-(U$7-SENSE)") (class "Default")
      (node (ref "L1") (pin "2") (pinfunction "2_2") (pintype "passive"))
      (node (ref "R4") (pin "1") (pinfunction "1_1") (pintype "passive"))
      (node (ref "U$7") (pin "P$10") (pinfunction "SENSE_P$10") (pintype "bidirectional"))
    )
    (net (code "27") (name "Net-(U$7-SW)") (class "Default")
      (node (ref "C25") (pin "1") (pinfunction "1_1") (pintype "passive"))
      (node (ref "D6") (pin "C") (pinfunction "C_C") (pintype "passive"))
      (node (ref "L1") (pin "1") (pinfunction "1_1") (pintype "passive"))
      (node (ref "U$7") (pin "P$12") (pinfunction "SW_P$12") (pintype "bidirectional"))
    )
    (net (code "28") (name "SUM_UVW") (class "Default")
      (node (ref "IC1") (pin "40") (pinfunction "PA0_40") (pintype "bidirectional"))
      (node (ref "R19") (pin "2") (pinfunction "2_2") (pintype "passive"))
      (node (ref "R20") (pin "2") (pinfunction "2_2") (pintype "passive"))
      (node (ref "R21") (pin "2") (pinfunction "2_2") (pintype "passive"))
    )
    (net (code "29") (name "U") (class "Default")
      (node (ref "C3") (pin "1") (pinfunction "1_1") (pintype "passive"))
      (node (ref "R13") (pin "1") (pinfunction "1_1") (pintype "passive"))
      (node (ref "U$1") (pin "TGR") (pinfunction "TGR_TGR") (pintype "passive"))
      (node (ref "U$4") (pin "7") (pinfunction "SWN_7") (pintype "passive"))
    )
    (net (code "30") (name "U_DISABLE_DRIVE") (class "Default")
      (node (ref "IC1") (pin "10") (pinfunction "PC0_10") (pintype "bidirectional"))
      (node (ref "U$4") (pin "3") (pinfunction "/OD_3") (pintype "passive"))
    )
    (net (code "31") (name "U_GATE_HIGH") (class "Default")
      (node (ref "U$1") (pin "TG") (pinfunction "TG_TG") (pintype "passive"))
      (node (ref "U$4") (pin "8") (pinfunction "DRVH_8") (pintype "passive"))
    )
    (net (code "32") (name "U_LOW_GATE") (class "Default")
      (node (ref "U$1") (pin "BG") (pinfunction "BG_BG") (pintype "passive"))
      (node (ref "U$4") (pin "5") (pinfunction "DRVL_5") (pintype "passive"))
    )
    (net (code "33") (name "U_PWM_DRIVE") (class "Default")
      (node (ref "IC1") (pin "11") (pinfunction "PC1_11") (pintype "bidirectional"))
      (node (ref "U$4") (pin "2") (pinfunction "IN_2") (pintype "passive"))
    )
    (net (code "34") (name "V") (class "Default")
      (node (ref "C2") (pin "1") (pinfunction "1_1") (pintype "passive"))
      (node (ref "R14") (pin "1") (pinfunction "1_1") (pintype "passive"))
      (node (ref "U$2") (pin "TGR") (pinfunction "TGR_TGR") (pintype "passive"))
      (node (ref "U$5") (pin "7") (pinfunction "SWN_7") (pintype "passive"))
    )
    (net (code "35") (name "VCC") (class "Default")
      (node (ref "C15") (pin "2") (pinfunction "2_2") (pintype "passive"))
      (node (ref "C16") (pin "+") (pinfunction "+_+") (pintype "passive"))
      (node (ref "C17") (pin "+") (pinfunction "+_+") (pintype "passive"))
      (node (ref "C19") (pin "1") (pinfunction "1_1") (pintype "passive"))
      (node (ref "C26") (pin "2") (pinfunction "2_2") (pintype "passive"))
      (node (ref "D4") (pin "C") (pinfunction "C_C") (pintype "passive"))
      (node (ref "R12") (pin "1") (pinfunction "1_1") (pintype "passive"))
      (node (ref "TP1") (pin "TP") (pinfunction "PP_TP") (pintype "input"))
      (node (ref "TP2") (pin "TP") (pinfunction "PP_TP") (pintype "input"))
      (node (ref "TP3") (pin "TP") (pinfunction "PP_TP") (pintype "input"))
      (node (ref "TP4") (pin "TP") (pinfunction "PP_TP") (pintype "input"))
      (node (ref "U$1") (pin "VIN") (pinfunction "VIN_VIN") (pintype "passive"))
      (node (ref "U$2") (pin "VIN") (pinfunction "VIN_VIN") (pintype "passive"))
      (node (ref "U$3") (pin "VIN") (pinfunction "VIN_VIN") (pintype "passive"))
      (node (ref "U$7") (pin "P$1") (pinfunction "VIN_P$1") (pintype "power_in"))
      (node (ref "U$7") (pin "P$2") (pinfunction "CLP_P$2") (pintype "bidirectional"))
      (node (ref "U$7") (pin "P$3") (pinfunction "/SHDN_P$3") (pintype "bidirectional"))
      (node (ref "U1") (pin "2") (pinfunction "IN_2") (pintype "power_in"))
    )
    (net (code "36") (name "V_DISABLE_DRIVE") (class "Default")
      (node (ref "IC1") (pin "12") (pinfunction "PC2_12") (pintype "bidirectional"))
      (node (ref "U$5") (pin "3") (pinfunction "/OD_3") (pintype "passive"))
    )
    (net (code "37") (name "V_HIGH_GATE") (class "Default")
      (node (ref "U$2") (pin "TG") (pinfunction "TG_TG") (pintype "passive"))
      (node (ref "U$5") (pin "8") (pinfunction "DRVH_8") (pintype "passive"))
    )
    (net (code "38") (name "V_LOW_GATE") (class "Default")
      (node (ref "U$2") (pin "BG") (pinfunction "BG_BG") (pintype "passive"))
      (node (ref "U$5") (pin "5") (pinfunction "DRVL_5") (pintype "passive"))
    )
    (net (code "39") (name "V_PWM_DRIVE") (class "Default")
      (node (ref "IC1") (pin "13") (pinfunction "PC3_13") (pintype "bidirectional"))
      (node (ref "U$5") (pin "2") (pinfunction "IN_2") (pintype "passive"))
    )
    (net (code "40") (name "W") (class "Default")
      (node (ref "C4") (pin "1") (pinfunction "1_1") (pintype "passive"))
      (node (ref "R15") (pin "1") (pinfunction "1_1") (pintype "passive"))
      (node (ref "U$3") (pin "TGR") (pinfunction "TGR_TGR") (pintype "passive"))
      (node (ref "U$6") (pin "7") (pinfunction "SWN_7") (pintype "passive"))
    )
    (net (code "41") (name "W_DISABLE_DRIVE") (class "Default")
      (node (ref "IC1") (pin "14") (pinfunction "PC4_14") (pintype "bidirectional"))
      (node (ref "U$6") (pin "3") (pinfunction "/OD_3") (pintype "passive"))
    )
    (net (code "42") (name "W_HIGH_GATE") (class "Default")
      (node (ref "U$3") (pin "TG") (pinfunction "TG_TG") (pintype "passive"))
      (node (ref "U$6") (pin "8") (pinfunction "DRVH_8") (pintype "passive"))
    )
    (net (code "43") (name "W_LOW_GATE") (class "Default")
      (node (ref "U$3") (pin "BG") (pinfunction "BG_BG") (pintype "passive"))
      (node (ref "U$6") (pin "5") (pinfunction "DRVL_5") (pintype "passive"))
    )
    (net (code "44") (name "W_PWM_DRIVE") (class "Default")
      (node (ref "IC1") (pin "15") (pinfunction "PC5_15") (pintype "bidirectional"))
      (node (ref "U$6") (pin "2") (pinfunction "IN_2") (pintype "passive"))
    )
    (net (code "45") (name "unconnected-(IC1-PB1-Pad5)") (class "Default")
      (node (ref "IC1") (pin "5") (pinfunction "PB1_5") (pintype "bidirectional"))
    )
    (net (code "46") (name "unconnected-(IC1-PB2-Pad6)") (class "Default")
      (node (ref "IC1") (pin "6") (pinfunction "PB2_6") (pintype "bidirectional"))
    )
    (net (code "47") (name "unconnected-(IC1-PB3-Pad7)") (class "Default")
      (node (ref "IC1") (pin "7") (pinfunction "PB3_7") (pintype "bidirectional"))
    )
    (net (code "48") (name "unconnected-(IC1-PC6-Pad16)") (class "Default")
      (node (ref "IC1") (pin "16") (pinfunction "PC6_16") (pintype "bidirectional"))
    )
    (net (code "49") (name "unconnected-(IC1-PC7-Pad17)") (class "Default")
      (node (ref "IC1") (pin "17") (pinfunction "PC7_17") (pintype "bidirectional"))
    )
    (net (code "50") (name "unconnected-(IC1-PD0-Pad20)") (class "Default")
      (node (ref "IC1") (pin "20") (pinfunction "PD0_20") (pintype "bidirectional"))
    )
    (net (code "51") (name "unconnected-(IC1-PD1-Pad21)") (class "Default")
      (node (ref "IC1") (pin "21") (pinfunction "PD1_21") (pintype "bidirectional"))
    )
    (net (code "52") (name "unconnected-(IC1-PD4-Pad24)") (class "Default")
      (node (ref "IC1") (pin "24") (pinfunction "PD4_24") (pintype "bidirectional"))
    )
    (net (code "53") (name "unconnected-(IC1-PD5-Pad25)") (class "Default")
      (node (ref "IC1") (pin "25") (pinfunction "PD5_25") (pintype "bidirectional"))
    )
    (net (code "54") (name "unconnected-(IC1-PE0-Pad28)") (class "Default")
      (node (ref "IC1") (pin "28") (pinfunction "PE0_28") (pintype "bidirectional"))
    )
    (net (code "55") (name "unconnected-(IC1-PE1-Pad29)") (class "Default")
      (node (ref "IC1") (pin "29") (pinfunction "PE1_29") (pintype "bidirectional"))
    )
    (net (code "56") (name "unconnected-(IC1-PE2-Pad32)") (class "Default")
      (node (ref "IC1") (pin "32") (pinfunction "PE2_32") (pintype "bidirectional"))
    )
    (net (code "57") (name "unconnected-(IC1-PR0(XT2)-Pad36)") (class "Default")
      (node (ref "IC1") (pin "36") (pinfunction "PR0(XT2)_36") (pintype "bidirectional"))
    )
    (net (code "58") (name "unconnected-(IC1-PR1(XT1)-Pad37)") (class "Default")
      (node (ref "IC1") (pin "37") (pinfunction "PR1(XT1)_37") (pintype "bidirectional"))
    )
    (net (code "59") (name "unconnected-(J2-PadID)") (class "Default")
      (node (ref "J2") (pin "ID") (pinfunction "ID_ID") (pintype "bidirectional"))
    )
    (net (code "60") (name "unconnected-(U$7-NTC-PadP$8)") (class "Default")
      (node (ref "U$7") (pin "P$8") (pinfunction "NTC_P$8") (pintype "bidirectional"))
    )
    (net (code "61") (name "unconnected-(U$7-RNG{slash}SS-PadP$7)") (class "Default")
      (node (ref "U$7") (pin "P$7") (pinfunction "RNG/SS_P$7") (pintype "bidirectional"))
    )
    (net (code "62") (name "unconnected-(U$7-{slash}CHRG-PadP$4)") (class "Default")
      (node (ref "U$7") (pin "P$4") (pinfunction "/CHRG_P$4") (pintype "bidirectional"))
    )
    (net (code "63") (name "unconnected-(U$7-{slash}FAULT-PadP$5)") (class "Default")
      (node (ref "U$7") (pin "P$5") (pinfunction "/FAULT_P$5") (pintype "bidirectional"))
    )
    (net (code "64") (name "unconnected-(U3-P4-Pad4)") (class "Default")
      (node (ref "U3") (pin "4") (pinfunction "P4_4") (pintype "bidirectional"))
    )
  )
)
